# Arduino_extension_connectors.net
KiCad netlist of a schematic drawn in Altium Designer
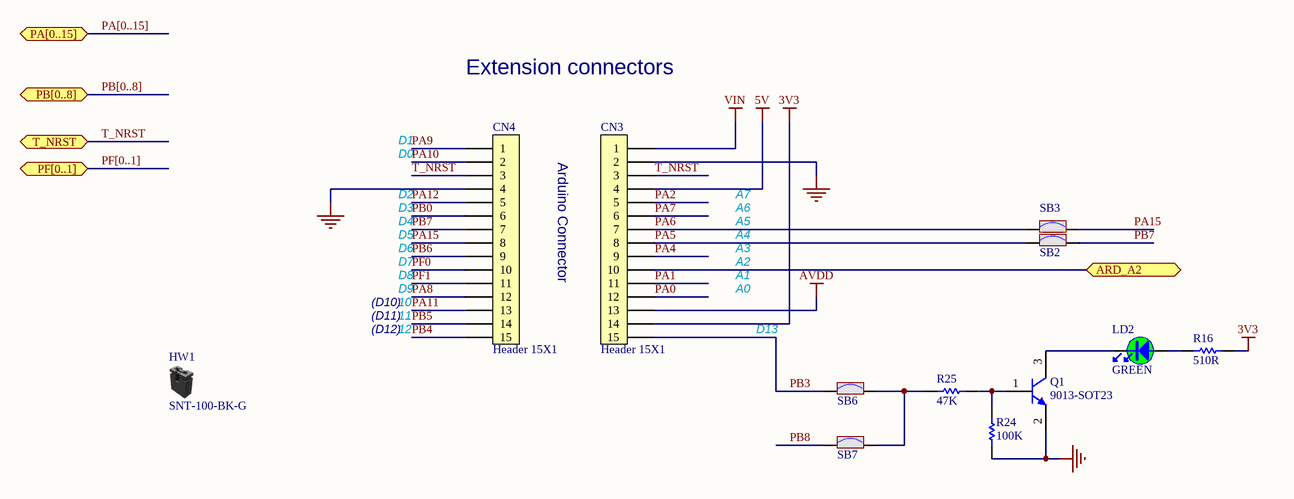
[diagram p0: Arduino_extension_connectors.SchDoc]

(export (version "E")
  (design (tool "Eeschema 10.0.6"))
  (components
    (comp (ref "CN3")
      (value "Header 15X1")
      (footprint "CON_LYCN_313115S161145")
      (description "Pin header, 15x1, 2,54mm, VR, TH, Height 6mm/6mm")
      (fields
        (field (name "INTERNAL_PART_NUMBER") "MCD-01332")
        (field (name "MANUFACTURER_PART_NUMBER") "313115S161145")
        (field (name "PROVIDED_BY") "SUBCO")
      )
      (libsource (lib "") (part "Header 15x1_1"))
    )
    (comp (ref "CN4")
      (value "Header 15X1")
      (footprint "CON_LYCN_313115S161145")
      (description "Pin header, 15x1, 2,54mm, VR, TH, Height 6mm/6mm")
      (fields
        (field (name "INTERNAL_PART_NUMBER") "MCD-01332")
        (field (name "MANUFACTURER_PART_NUMBER") "313115S161145")
        (field (name "PROVIDED_BY") "SUBCO")
      )
      (libsource (lib "MCD_PARTS_database") (part "Header 15x1"))
    )
    (comp (ref "HW1")
      (value "SNT-100-BK-G")
      (description "SHUNT 2.54mm BLACK")
      (fields
        (field (name "INTERNAL_PART_NUMBER") "MCD-00043")
        (field (name "MANUFACTURER") "SAMTEC")
        (field (name "PROVIDED_BY") "SUBCO")
      )
      (libsource (lib "MCD_PARTS_database") (part "Shunt Black 2.54mm"))
    )
    (comp (ref "LD2")
      (value "GREEN")
      (footprint "LED_0603_GREEN")
      (description "LED, Green, 0603")
      (fields
        (field (name "INTERNAL_PART_NUMBER") "MCD-00050")
        (field (name "MANUFACTURER_PART_NUMBER") "19-213SYGC/S530-E2/TR8")
        (field (name "PROVIDED_BY") "SUBCO")
      )
      (libsource (lib "MCD_PARTS_database") (part "LED_green"))
    )
    (comp (ref "Q1")
      (value "9013-SOT23")
      (footprint "NPN_SOT23")
      (description "NPN Bipolar Transistor")
      (fields
        (field (name "INTERNAL_PART_NUMBER") "MCD-00073")
        (field (name "MANUFACTURER_PART_NUMBER") "BSR14")
        (field (name "PROVIDED_BY") "SUBCO")
      )
      (libsource (lib "MCD_PARTS_database") (part "9013-SOT23"))
    )
    (comp (ref "R16")
      (value "510R")
      (footprint "R0402")
      (description "Resistor,510R,0402,1%,1/16W")
      (fields
        (field (name "INTERNAL_PART_NUMBER") "MCD-00064")
        (field (name "MANUFACTURER_PART_NUMBER") "RC0402FR-07510RL")
        (field (name "PROVIDED_BY") "SUBCO")
      )
      (libsource (lib "MCD_PARTS_database") (part "Resistor"))
    )
    (comp (ref "R24")
      (value "100K")
      (footprint "R0402")
      (description "Resistor,100K,0402,1%,1/16W")
      (fields
        (field (name "INTERNAL_PART_NUMBER") "MCD-00059")
        (field (name "MANUFACTURER_PART_NUMBER") "RC0402FR-07100KL")
        (field (name "PROVIDED_BY") "SUBCO")
      )
      (libsource (lib "MCD_PARTS_database") (part "Resistor"))
    )
    (comp (ref "R25")
      (value "47K")
      (footprint "R0402")
      (description "Resistor,47K,0402,1%,1/16W")
      (fields
        (field (name "INTERNAL_PART_NUMBER") "MCD-00063")
        (field (name "MANUFACTURER_PART_NUMBER") "RC0402FR-0747KL")
        (field (name "PROVIDED_BY") "SUBCO")
      )
      (libsource (lib "MCD_PARTS_database") (part "Resistor"))
    )
    (comp (ref "SB2")
      (value "~")
      (footprint "SOLDER-BRIDGE_R0603-0R")
      (description "Solder Bridge ON")
      (fields
        (field (name "INTERNAL_PART_NUMBER") "MCD-00071")
        (field (name "MANUFACTURER_PART_NUMBER") "RC0603JR-070RL")
        (field (name "PROVIDED_BY") "SUBCO")
      )
      (libsource (lib "MCD_PARTS_database") (part "SB_ON"))
    )
    (comp (ref "SB3")
      (value "~")
      (footprint "SOLDER-BRIDGE_R0603-0R")
      (description "Solder Bridge ON")
      (fields
        (field (name "INTERNAL_PART_NUMBER") "MCD-00071")
        (field (name "MANUFACTURER_PART_NUMBER") "RC0603JR-070RL")
        (field (name "PROVIDED_BY") "SUBCO")
      )
      (libsource (lib "MCD_PARTS_database") (part "SB_ON"))
    )
    (comp (ref "SB6")
      (value "~")
      (footprint "SOLDER-BRIDGE_R0603-0R")
      (description "Solder Bridge ON")
      (fields
        (field (name "INTERNAL_PART_NUMBER") "MCD-00071")
        (field (name "MANUFACTURER_PART_NUMBER") "RC0603JR-070RL")
        (field (name "PROVIDED_BY") "SUBCO")
      )
      (libsource (lib "MCD_PARTS_database") (part "SB_ON"))
    )
    (comp (ref "SB7")
      (value "~")
      (footprint "SOLDER-BRIDGE_R0603-0R")
      (description "Solder Bridge ON")
      (fields
        (field (name "INTERNAL_PART_NUMBER") "MCD-00071")
        (field (name "MANUFACTURER_PART_NUMBER") "RC0603JR-070RL")
        (field (name "PROVIDED_BY") "SUBCO")
      )
      (libsource (lib "MCD_PARTS_database") (part "SB_ON"))
    )
  )
  (nets
    (net (code "6") (name "/ARD_A2") (class "Default")
      (node (ref "CN3") (pin "10") (pinfunction "10_10") (pintype "passive"))
    )
    (net (code "7") (name "/PA0") (class "Default")
      (node (ref "CN3") (pin "12") (pinfunction "12_12") (pintype "passive"))
    )
    (net (code "8") (name "/PA1") (class "Default")
      (node (ref "CN3") (pin "11") (pinfunction "11_11") (pintype "passive"))
    )
    (net (code "9") (name "/PA2") (class "Default")
      (node (ref "CN3") (pin "5") (pinfunction "5_5") (pintype "passive"))
    )
    (net (code "10") (name "/PA4") (class "Default")
      (node (ref "CN3") (pin "9") (pinfunction "9_9") (pintype "passive"))
    )
    (net (code "11") (name "/PA5") (class "Default")
      (node (ref "CN3") (pin "8") (pinfunction "8_8") (pintype "passive"))
      (node (ref "SB2") (pin "1") (pinfunction "1_1") (pintype "passive"))
    )
    (net (code "12") (name "/PA6") (class "Default")
      (node (ref "CN3") (pin "7") (pinfunction "7_7") (pintype "passive"))
      (node (ref "SB3") (pin "1") (pinfunction "1_1") (pintype "passive"))
    )
    (net (code "13") (name "/PA7") (class "Default")
      (node (ref "CN3") (pin "6") (pinfunction "6_6") (pintype "passive"))
    )
    (net (code "14") (name "/PA8") (class "Default")
      (node (ref "CN4") (pin "12") (pinfunction "12_12") (pintype "passive"))
    )
    (net (code "15") (name "/PA9") (class "Default")
      (node (ref "CN4") (pin "1") (pinfunction "1_1") (pintype "passive"))
    )
    (net (code "16") (name "/PA10") (class "Default")
      (node (ref "CN4") (pin "2") (pinfunction "2_2") (pintype "passive"))
    )
    (net (code "17") (name "/PA11") (class "Default")
      (node (ref "CN4") (pin "13") (pinfunction "13_13") (pintype "passive"))
    )
    (net (code "18") (name "/PA12") (class "Default")
      (node (ref "CN4") (pin "5") (pinfunction "5_5") (pintype "passive"))
    )
    (net (code "19") (name "/PA15") (class "Default")
      (node (ref "CN4") (pin "8") (pinfunction "8_8") (pintype "passive"))
      (node (ref "SB3") (pin "2") (pinfunction "2_2") (pintype "passive"))
    )
    (net (code "21") (name "/PB0") (class "Default")
      (node (ref "CN4") (pin "6") (pinfunction "6_6") (pintype "passive"))
    )
    (net (code "22") (name "/PB3") (class "Default")
      (node (ref "CN3") (pin "15") (pinfunction "15_15") (pintype "passive"))
      (node (ref "SB6") (pin "1") (pinfunction "1_1") (pintype "passive"))
    )
    (net (code "23") (name "/PB4") (class "Default")
      (node (ref "CN4") (pin "15") (pinfunction "15_15") (pintype "passive"))
    )
    (net (code "24") (name "/PB5") (class "Default")
      (node (ref "CN4") (pin "14") (pinfunction "14_14") (pintype "passive"))
    )
    (net (code "25") (name "/PB6") (class "Default")
      (node (ref "CN4") (pin "9") (pinfunction "9_9") (pintype "passive"))
    )
    (net (code "26") (name "/PB7") (class "Default")
      (node (ref "CN4") (pin "7") (pinfunction "7_7") (pintype "passive"))
      (node (ref "SB2") (pin "2") (pinfunction "2_2") (pintype "passive"))
    )
    (net (code "27") (name "/PB8") (class "Default")
      (node (ref "SB7") (pin "1") (pinfunction "1_1") (pintype "passive"))
    )
    (net (code "29") (name "/PF0") (class "Default")
      (node (ref "CN4") (pin "10") (pinfunction "10_10") (pintype "passive"))
    )
    (net (code "30") (name "/PF1") (class "Default")
      (node (ref "CN4") (pin "11") (pinfunction "11_11") (pintype "passive"))
    )
    (net (code "32") (name "/T_NRST") (class "Default")
      (node (ref "CN3") (pin "3") (pinfunction "3_3") (pintype "passive"))
      (node (ref "CN4") (pin "3") (pinfunction "3_3") (pintype "passive"))
    )
    (net (code "33") (name "3V3") (class "Default")
      (node (ref "CN3") (pin "14") (pinfunction "14_14") (pintype "passive"))
      (node (ref "R16") (pin "2") (pinfunction "2_2") (pintype "passive"))
    )
    (net (code "34") (name "5V") (class "Default")
      (node (ref "CN3") (pin "4") (pinfunction "4_4") (pintype "passive"))
    )
    (net (code "35") (name "AVDD") (class "Default")
      (node (ref "CN3") (pin "13") (pinfunction "13_13") (pintype "passive"))
    )
    (net (code "36") (name "GND") (class "Default")
      (node (ref "CN3") (pin "2") (pinfunction "2_2") (pintype "passive"))
      (node (ref "CN4") (pin "4") (pinfunction "4_4") (pintype "passive"))
      (node (ref "Q1") (pin "2") (pinfunction "E_2") (pintype "passive"))
      (node (ref "R24") (pin "1") (pinfunction "1_1") (pintype "passive"))
    )
    (net (code "37") (name "Net-(LD2-Pad1)") (class "Default")
      (node (ref "LD2") (pin "1") (pintype "passive"))
      (node (ref "R16") (pin "1") (pinfunction "1_1") (pintype "passive"))
    )
    (net (code "38") (name "Net-(Q1-B)") (class "Default")
      (node (ref "Q1") (pin "1") (pinfunction "B_1") (pintype "passive"))
      (node (ref "R24") (pin "2") (pinfunction "2_2") (pintype "passive"))
      (node (ref "R25") (pin "2") (pinfunction "2_2") (pintype "passive"))
    )
    (net (code "39") (name "Net-(Q1-C)") (class "Default")
      (node (ref "LD2") (pin "2") (pintype "passive"))
      (node (ref "Q1") (pin "3") (pinfunction "C_3") (pintype "passive"))
    )
    (net (code "40") (name "Net-(R25-Pad1)") (class "Default")
      (node (ref "R25") (pin "1") (pinfunction "1_1") (pintype "passive"))
      (node (ref "SB6") (pin "2") (pinfunction "2_2") (pintype "passive"))
      (node (ref "SB7") (pin "2") (pinfunction "2_2") (pintype "passive"))
    )
    (net (code "41") (name "VIN") (class "Default")
      (node (ref "CN3") (pin "1") (pinfunction "1_1") (pintype "passive"))
    )
  )
)
